# picostepknobs_dispoffset.net
KiCad netlist of a schematic drawn in EAGLE
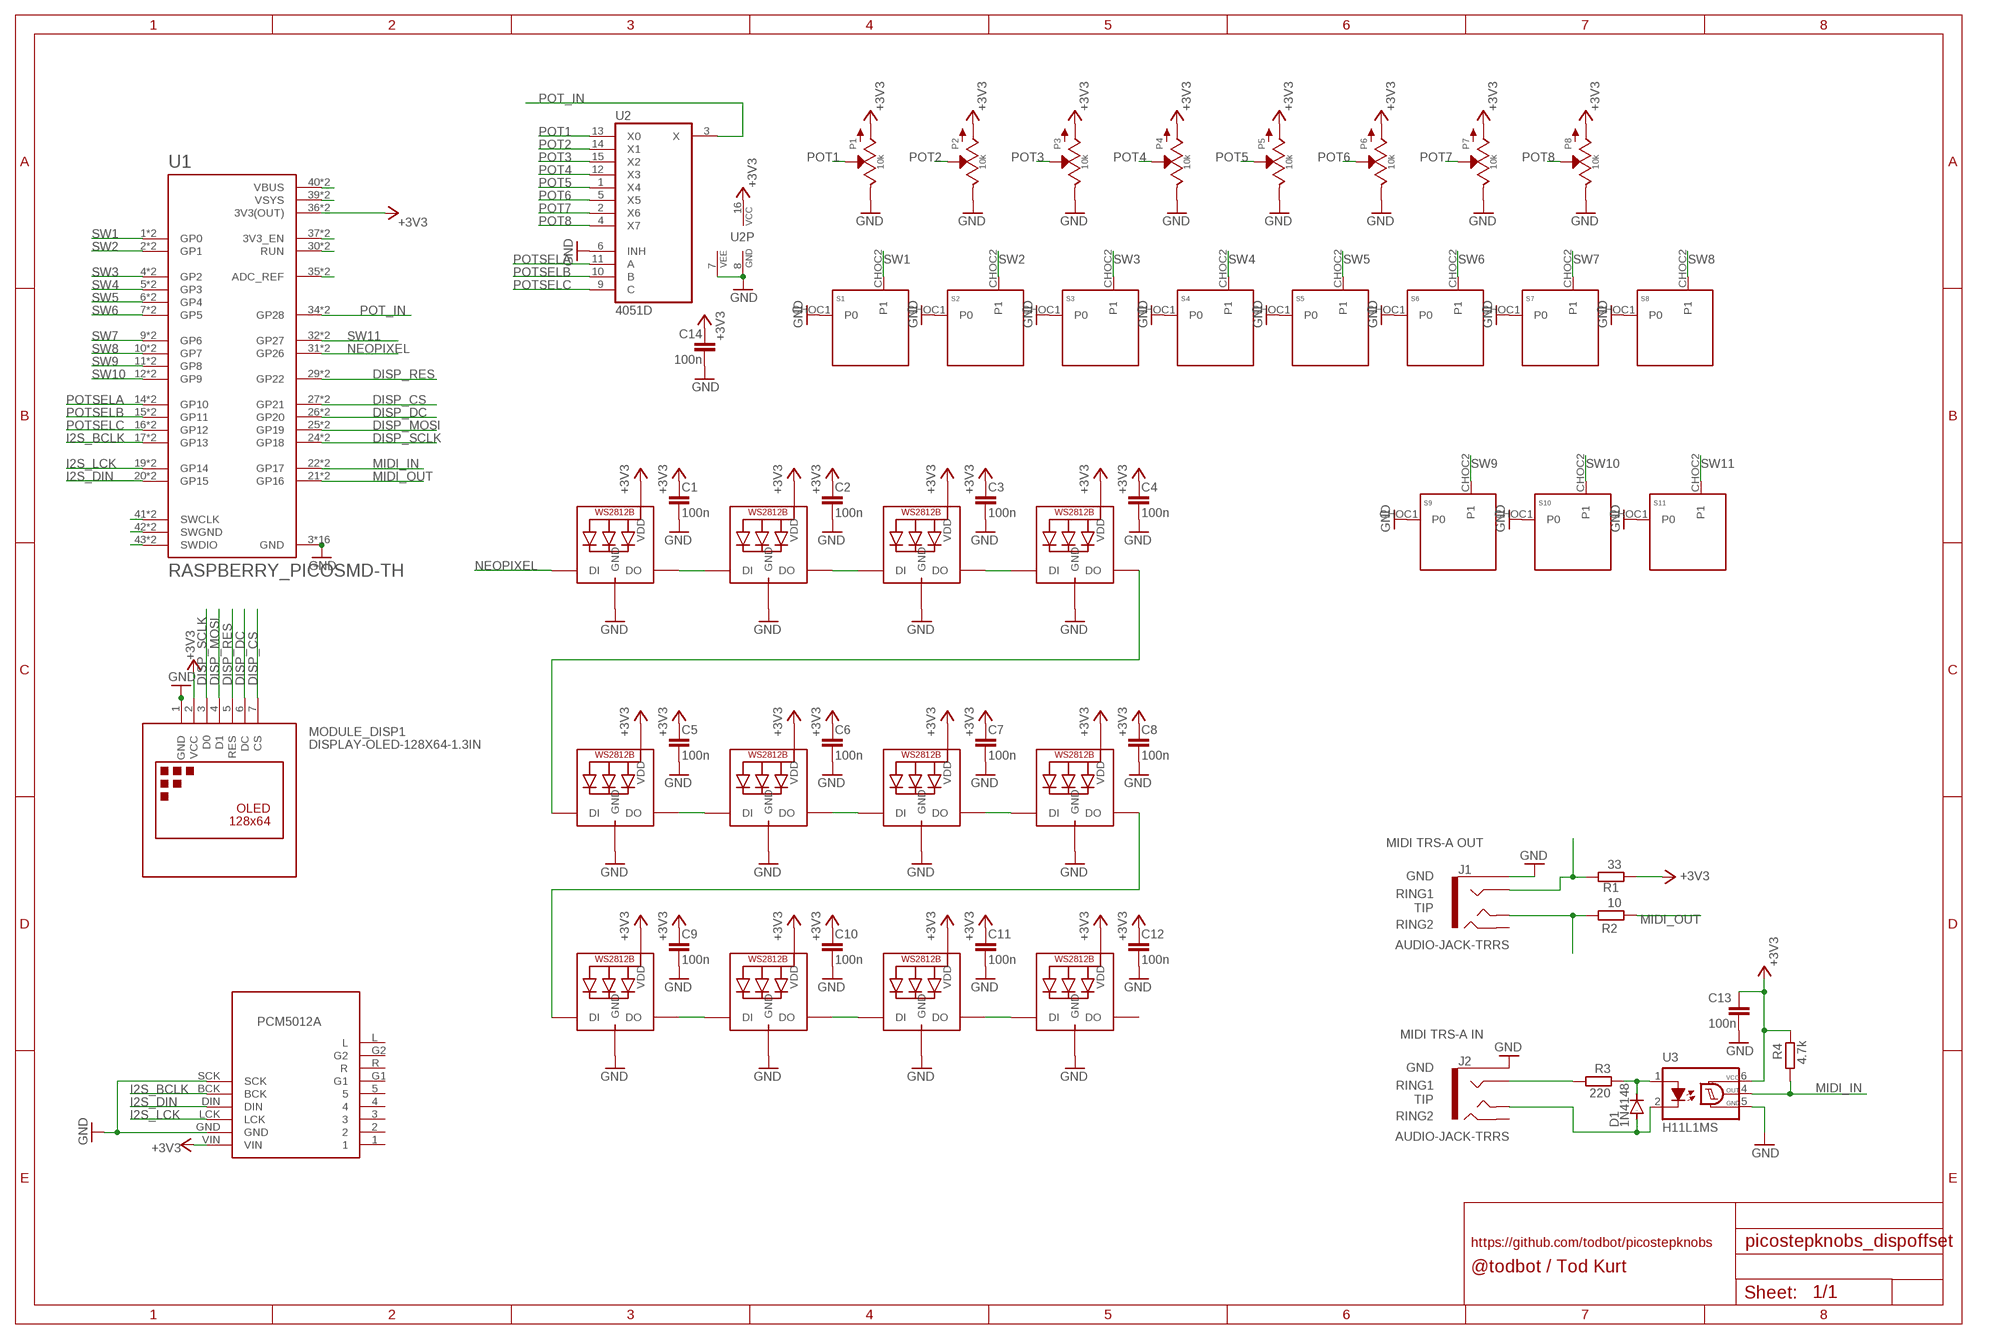
[diagram p0: schematic, sheet 1]

(export (version "E")
  (design (tool "Eeschema 10.0.6"))
  (components
    (comp (ref "C1")
      (value "100n")
      (footprint "eagle-import:C0805")
      (libsource (lib "eagle-import") (part "C-EUC0805"))
    )
    (comp (ref "C2")
      (value "100n")
      (footprint "eagle-import:C0805")
      (libsource (lib "eagle-import") (part "C-EUC0805"))
    )
    (comp (ref "C3")
      (value "100n")
      (footprint "eagle-import:C0805")
      (libsource (lib "eagle-import") (part "C-EUC0805"))
    )
    (comp (ref "C4")
      (value "100n")
      (footprint "eagle-import:C0805")
      (libsource (lib "eagle-import") (part "C-EUC0805"))
    )
    (comp (ref "C5")
      (value "100n")
      (footprint "eagle-import:C0805")
      (libsource (lib "eagle-import") (part "C-EUC0805"))
    )
    (comp (ref "C6")
      (value "100n")
      (footprint "eagle-import:C0805")
      (libsource (lib "eagle-import") (part "C-EUC0805"))
    )
    (comp (ref "C7")
      (value "100n")
      (footprint "eagle-import:C0805")
      (libsource (lib "eagle-import") (part "C-EUC0805"))
    )
    (comp (ref "C8")
      (value "100n")
      (footprint "eagle-import:C0805")
      (libsource (lib "eagle-import") (part "C-EUC0805"))
    )
    (comp (ref "C9")
      (value "100n")
      (footprint "eagle-import:C0805")
      (libsource (lib "eagle-import") (part "C-EUC0805"))
    )
    (comp (ref "C10")
      (value "100n")
      (footprint "eagle-import:C0805")
      (libsource (lib "eagle-import") (part "C-EUC0805"))
    )
    (comp (ref "C11")
      (value "100n")
      (footprint "eagle-import:C0805")
      (libsource (lib "eagle-import") (part "C-EUC0805"))
    )
    (comp (ref "C12")
      (value "100n")
      (footprint "eagle-import:C0805")
      (libsource (lib "eagle-import") (part "C-EUC0805"))
    )
    (comp (ref "C13")
      (value "100n")
      (footprint "eagle-import:C0805")
      (libsource (lib "eagle-import") (part "C-EUC0805"))
    )
    (comp (ref "C14")
      (value "100n")
      (footprint "eagle-import:C0805")
      (libsource (lib "eagle-import") (part "C-EUC0805"))
    )
    (comp (ref "D1")
      (value "1N4148")
      (footprint "eagle-import:SOD123")
      (libsource (lib "eagle-import") (part "DIODE-SOD123"))
    )
    (comp (ref "J1")
      (value "AUDIO-JACK-TRRS")
      (footprint "eagle-import:PJ-320D_SPARKFUN")
      (fields (field (name "MPN") "PJ-320D") (field (name "LCSC") "C431535"))
      (libsource (lib "eagle-import") (part "AUDIO-JACK-TRRS"))
    )
    (comp (ref "J2")
      (value "AUDIO-JACK-TRRS")
      (footprint "eagle-import:PJ-320D_SPARKFUN")
      (fields (field (name "MPN") "PJ-320D"))
      (libsource (lib "eagle-import") (part "AUDIO-JACK-TRRS"))
    )
    (comp (ref "LED1")
      (value "WS2812B3535")
      (footprint "eagle-import:LED3535")
      (libsource (lib "eagle-import") (part "WS2812B3535"))
    )
    (comp (ref "LED2")
      (value "WS2812B3535")
      (footprint "eagle-import:LED3535")
      (libsource (lib "eagle-import") (part "WS2812B3535"))
    )
    (comp (ref "LED3")
      (value "WS2812B3535")
      (footprint "eagle-import:LED3535")
      (libsource (lib "eagle-import") (part "WS2812B3535"))
    )
    (comp (ref "LED4")
      (value "WS2812B3535")
      (footprint "eagle-import:LED3535")
      (libsource (lib "eagle-import") (part "WS2812B3535"))
    )
    (comp (ref "LED5")
      (value "WS2812B3535")
      (footprint "eagle-import:LED3535")
      (libsource (lib "eagle-import") (part "WS2812B3535"))
    )
    (comp (ref "LED6")
      (value "WS2812B3535")
      (footprint "eagle-import:LED3535")
      (libsource (lib "eagle-import") (part "WS2812B3535"))
    )
    (comp (ref "LED7")
      (value "WS2812B3535")
      (footprint "eagle-import:LED3535")
      (libsource (lib "eagle-import") (part "WS2812B3535"))
    )
    (comp (ref "LED8")
      (value "WS2812B3535")
      (footprint "eagle-import:LED3535")
      (libsource (lib "eagle-import") (part "WS2812B3535"))
    )
    (comp (ref "LED9")
      (value "WS2812B3535")
      (footprint "eagle-import:LED3535")
      (libsource (lib "eagle-import") (part "WS2812B3535"))
    )
    (comp (ref "LED10")
      (value "WS2812B3535")
      (footprint "eagle-import:LED3535")
      (libsource (lib "eagle-import") (part "WS2812B3535"))
    )
    (comp (ref "LED11")
      (value "WS2812B3535")
      (footprint "eagle-import:LED3535")
      (libsource (lib "eagle-import") (part "WS2812B3535"))
    )
    (comp (ref "LED12")
      (value "WS2812B3535")
      (footprint "eagle-import:LED3535")
      (libsource (lib "eagle-import") (part "WS2812B3535"))
    )
    (comp (ref "MODULE_DISP1")
      (value "DISPLAY-OLED-128X64-1.3IN")
      (footprint "eagle-import:DISPLAY-OLED-128X64-1.3IN")
      (libsource (lib "eagle-import") (part "DISPLAY-OLED-128X64-1.3IN"))
    )
    (comp (ref "MODULE_PCM5102A")
      (value "I2S_PCM_51XX_SOUNDCARD")
      (footprint "eagle-import:I2S_PCM_5100_SOUNDCARD")
      (libsource (lib "eagle-import") (part "I2S_PCM_51XX_SOUNDCARD"))
    )
    (comp (ref "P1")
      (value "10k")
      (footprint "eagle-import:OG-POTS_ALPS_POT_VERTICAL_WITHBIGKNOB")
      (libsource (lib "eagle-import") (part "POTZEPHPOT_BIGKNOB"))
    )
    (comp (ref "P2")
      (value "10k")
      (footprint "eagle-import:OG-POTS_ALPS_POT_VERTICAL_WITHBIGKNOB")
      (libsource (lib "eagle-import") (part "POTZEPHPOT_BIGKNOB"))
    )
    (comp (ref "P3")
      (value "10k")
      (footprint "eagle-import:OG-POTS_ALPS_POT_VERTICAL_WITHBIGKNOB")
      (libsource (lib "eagle-import") (part "POTZEPHPOT_BIGKNOB"))
    )
    (comp (ref "P4")
      (value "10k")
      (footprint "eagle-import:OG-POTS_ALPS_POT_VERTICAL_WITHBIGKNOB")
      (libsource (lib "eagle-import") (part "POTZEPHPOT_BIGKNOB"))
    )
    (comp (ref "P5")
      (value "10k")
      (footprint "eagle-import:OG-POTS_ALPS_POT_VERTICAL_WITHBIGKNOB")
      (libsource (lib "eagle-import") (part "POTZEPHPOT_BIGKNOB"))
    )
    (comp (ref "P6")
      (value "10k")
      (footprint "eagle-import:OG-POTS_ALPS_POT_VERTICAL_WITHBIGKNOB")
      (libsource (lib "eagle-import") (part "POTZEPHPOT_BIGKNOB"))
    )
    (comp (ref "P7")
      (value "10k")
      (footprint "eagle-import:OG-POTS_ALPS_POT_VERTICAL_WITHBIGKNOB")
      (libsource (lib "eagle-import") (part "POTZEPHPOT_BIGKNOB"))
    )
    (comp (ref "P8")
      (value "10k")
      (footprint "eagle-import:OG-POTS_ALPS_POT_VERTICAL_WITHBIGKNOB")
      (libsource (lib "eagle-import") (part "POTZEPHPOT_BIGKNOB"))
    )
    (comp (ref "R1")
      (value "33")
      (footprint "eagle-import:R0805")
      (libsource (lib "eagle-import") (part "R-EU_R0805"))
    )
    (comp (ref "R2")
      (value "10")
      (footprint "eagle-import:R0805")
      (libsource (lib "eagle-import") (part "R-EU_R0805"))
    )
    (comp (ref "R3")
      (value "220")
      (footprint "eagle-import:R0805")
      (libsource (lib "eagle-import") (part "R-EU_R0805"))
    )
    (comp (ref "R4")
      (value "4.7k")
      (footprint "eagle-import:R0805")
      (libsource (lib "eagle-import") (part "R-EU_R0805"))
    )
    (comp (ref "S1")
      (value "KEYSWITCH-PLAIN-CHOC-1U")
      (footprint "eagle-import:CHOC-1U")
      (libsource (lib "eagle-import") (part "KEYSWITCH-PLAIN-CHOC-1U"))
    )
    (comp (ref "S2")
      (value "KEYSWITCH-PLAIN-CHOC-1U")
      (footprint "eagle-import:CHOC-1U")
      (libsource (lib "eagle-import") (part "KEYSWITCH-PLAIN-CHOC-1U"))
    )
    (comp (ref "S3")
      (value "KEYSWITCH-PLAIN-CHOC-1U")
      (footprint "eagle-import:CHOC-1U")
      (libsource (lib "eagle-import") (part "KEYSWITCH-PLAIN-CHOC-1U"))
    )
    (comp (ref "S4")
      (value "KEYSWITCH-PLAIN-CHOC-1U")
      (footprint "eagle-import:CHOC-1U")
      (libsource (lib "eagle-import") (part "KEYSWITCH-PLAIN-CHOC-1U"))
    )
    (comp (ref "S5")
      (value "KEYSWITCH-PLAIN-CHOC-1U")
      (footprint "eagle-import:CHOC-1U")
      (libsource (lib "eagle-import") (part "KEYSWITCH-PLAIN-CHOC-1U"))
    )
    (comp (ref "S6")
      (value "KEYSWITCH-PLAIN-CHOC-1U")
      (footprint "eagle-import:CHOC-1U")
      (libsource (lib "eagle-import") (part "KEYSWITCH-PLAIN-CHOC-1U"))
    )
    (comp (ref "S7")
      (value "KEYSWITCH-PLAIN-CHOC-1U")
      (footprint "eagle-import:CHOC-1U")
      (libsource (lib "eagle-import") (part "KEYSWITCH-PLAIN-CHOC-1U"))
    )
    (comp (ref "S8")
      (value "KEYSWITCH-PLAIN-CHOC-1U")
      (footprint "eagle-import:CHOC-1U")
      (libsource (lib "eagle-import") (part "KEYSWITCH-PLAIN-CHOC-1U"))
    )
    (comp (ref "S9")
      (value "KEYSWITCH-PLAIN-CHOC-1U")
      (footprint "eagle-import:CHOC-1U")
      (libsource (lib "eagle-import") (part "KEYSWITCH-PLAIN-CHOC-1U"))
    )
    (comp (ref "S10")
      (value "KEYSWITCH-PLAIN-CHOC-1U")
      (footprint "eagle-import:CHOC-1U")
      (libsource (lib "eagle-import") (part "KEYSWITCH-PLAIN-CHOC-1U"))
    )
    (comp (ref "S11")
      (value "KEYSWITCH-PLAIN-CHOC-1U")
      (footprint "eagle-import:CHOC-1U")
      (libsource (lib "eagle-import") (part "KEYSWITCH-PLAIN-CHOC-1U"))
    )
    (comp (ref "U1")
      (value "RASPBERRY_PICOSMD-TH")
      (footprint "eagle-import:PICO-PKG")
      (libsource (lib "eagle-import") (part "RASPBERRY_PICOSMD-TH"))
    )
    (comp (ref "U2")
      (value "4051D")
      (footprint "eagle-import:SO16")
      (libsource (lib "eagle-import") (part "4051D"))
    )
    (comp (ref "U3")
      (value "H11L1MS")
      (footprint "eagle-import:DIL6-SMD")
      (libsource (lib "eagle-import") (part "H11LMS1"))
    )
  )
  (nets
    (net (code "1") (name "+3V3") (class "Default")
      (node (ref "C1") (pin "1") (pinfunction "1_1") (pintype "passive"))
      (node (ref "C10") (pin "1") (pinfunction "1_1") (pintype "passive"))
      (node (ref "C11") (pin "1") (pinfunction "1_1") (pintype "passive"))
      (node (ref "C12") (pin "1") (pinfunction "1_1") (pintype "passive"))
      (node (ref "C13") (pin "1") (pinfunction "1_1") (pintype "passive"))
      (node (ref "C14") (pin "1") (pinfunction "1_1") (pintype "passive"))
      (node (ref "C2") (pin "1") (pinfunction "1_1") (pintype "passive"))
      (node (ref "C3") (pin "1") (pinfunction "1_1") (pintype "passive"))
      (node (ref "C4") (pin "1") (pinfunction "1_1") (pintype "passive"))
      (node (ref "C5") (pin "1") (pinfunction "1_1") (pintype "passive"))
      (node (ref "C6") (pin "1") (pinfunction "1_1") (pintype "passive"))
      (node (ref "C7") (pin "1") (pinfunction "1_1") (pintype "passive"))
      (node (ref "C8") (pin "1") (pinfunction "1_1") (pintype "passive"))
      (node (ref "C9") (pin "1") (pinfunction "1_1") (pintype "passive"))
      (node (ref "LED1") (pin "2") (pinfunction "VDD_2") (pintype "power_in"))
      (node (ref "LED10") (pin "2") (pinfunction "VDD_2") (pintype "power_in"))
      (node (ref "LED11") (pin "2") (pinfunction "VDD_2") (pintype "power_in"))
      (node (ref "LED12") (pin "2") (pinfunction "VDD_2") (pintype "power_in"))
      (node (ref "LED2") (pin "2") (pinfunction "VDD_2") (pintype "power_in"))
      (node (ref "LED3") (pin "2") (pinfunction "VDD_2") (pintype "power_in"))
      (node (ref "LED4") (pin "2") (pinfunction "VDD_2") (pintype "power_in"))
      (node (ref "LED5") (pin "2") (pinfunction "VDD_2") (pintype "power_in"))
      (node (ref "LED6") (pin "2") (pinfunction "VDD_2") (pintype "power_in"))
      (node (ref "LED7") (pin "2") (pinfunction "VDD_2") (pintype "power_in"))
      (node (ref "LED8") (pin "2") (pinfunction "VDD_2") (pintype "power_in"))
      (node (ref "LED9") (pin "2") (pinfunction "VDD_2") (pintype "power_in"))
      (node (ref "MODULE_DISP1") (pin "2") (pinfunction "VCC_2") (pintype "power_in"))
      (node (ref "MODULE_PCM5102A") (pin "VIN") (pinfunction "VIN_VIN") (pintype "bidirectional"))
      (node (ref "P1") (pin "P$3") (pinfunction "A_P$3") (pintype "passive"))
      (node (ref "P2") (pin "P$3") (pinfunction "A_P$3") (pintype "passive"))
      (node (ref "P3") (pin "P$3") (pinfunction "A_P$3") (pintype "passive"))
      (node (ref "P4") (pin "P$3") (pinfunction "A_P$3") (pintype "passive"))
      (node (ref "P5") (pin "P$3") (pinfunction "A_P$3") (pintype "passive"))
      (node (ref "P6") (pin "P$3") (pinfunction "A_P$3") (pintype "passive"))
      (node (ref "P7") (pin "P$3") (pinfunction "A_P$3") (pintype "passive"))
      (node (ref "P8") (pin "P$3") (pinfunction "A_P$3") (pintype "passive"))
      (node (ref "R1") (pin "2") (pinfunction "2_2") (pintype "passive"))
      (node (ref "R4") (pin "1") (pinfunction "1_1") (pintype "passive"))
      (node (ref "U1") (pin "36") (pinfunction "3V3(OUT)_36") (pintype "power_in"))
      (node (ref "U1") (pin "P$36") (pinfunction "3V3(OUT)_P$36") (pintype "power_in"))
      (node (ref "U2") (pin "16") (pinfunction "VCC_16") (pintype "power_in"))
      (node (ref "U3") (pin "6") (pinfunction "VCC_6") (pintype "power_in"))
    )
    (net (code "2") (name "/DISP_CS") (class "Default")
      (node (ref "MODULE_DISP1") (pin "7") (pinfunction "CS_7") (pintype "bidirectional"))
      (node (ref "U1") (pin "27") (pinfunction "GP21_27") (pintype "bidirectional"))
      (node (ref "U1") (pin "P$27") (pinfunction "GP21_P$27") (pintype "bidirectional"))
    )
    (net (code "3") (name "/DISP_DC") (class "Default")
      (node (ref "MODULE_DISP1") (pin "6") (pinfunction "DC_6") (pintype "bidirectional"))
      (node (ref "U1") (pin "26") (pinfunction "GP20_26") (pintype "bidirectional"))
      (node (ref "U1") (pin "P$26") (pinfunction "GP20_P$26") (pintype "bidirectional"))
    )
    (net (code "4") (name "/DISP_MOSI") (class "Default")
      (node (ref "MODULE_DISP1") (pin "4") (pinfunction "D1_4") (pintype "bidirectional"))
      (node (ref "U1") (pin "25") (pinfunction "GP19_25") (pintype "bidirectional"))
      (node (ref "U1") (pin "P$25") (pinfunction "GP19_P$25") (pintype "bidirectional"))
    )
    (net (code "5") (name "/DISP_RES") (class "Default")
      (node (ref "MODULE_DISP1") (pin "5") (pinfunction "RES_5") (pintype "bidirectional"))
      (node (ref "U1") (pin "29") (pinfunction "GP22_29") (pintype "bidirectional"))
      (node (ref "U1") (pin "P$29") (pinfunction "GP22_P$29") (pintype "bidirectional"))
    )
    (net (code "6") (name "/DISP_SCLK") (class "Default")
      (node (ref "MODULE_DISP1") (pin "3") (pinfunction "D0_3") (pintype "bidirectional"))
      (node (ref "U1") (pin "24") (pinfunction "GP18_24") (pintype "bidirectional"))
      (node (ref "U1") (pin "P$24") (pinfunction "GP18_P$24") (pintype "bidirectional"))
    )
    (net (code "7") (name "/I2S_BCLK") (class "Default")
      (node (ref "MODULE_PCM5102A") (pin "BCK") (pinfunction "BCK_BCK") (pintype "bidirectional"))
      (node (ref "U1") (pin "17") (pinfunction "GP13_17") (pintype "bidirectional"))
      (node (ref "U1") (pin "P$17") (pinfunction "GP13_P$17") (pintype "bidirectional"))
    )
    (net (code "8") (name "/I2S_DIN") (class "Default")
      (node (ref "MODULE_PCM5102A") (pin "DIN") (pinfunction "DIN_DIN") (pintype "bidirectional"))
      (node (ref "U1") (pin "20") (pinfunction "GP15_20") (pintype "bidirectional"))
      (node (ref "U1") (pin "P$20") (pinfunction "GP15_P$20") (pintype "bidirectional"))
    )
    (net (code "9") (name "/I2S_LCK") (class "Default")
      (node (ref "MODULE_PCM5102A") (pin "LCK") (pinfunction "LCK_LCK") (pintype "bidirectional"))
      (node (ref "U1") (pin "19") (pinfunction "GP14_19") (pintype "bidirectional"))
      (node (ref "U1") (pin "P$19") (pinfunction "GP14_P$19") (pintype "bidirectional"))
    )
    (net (code "10") (name "/MIDI_IN") (class "Default")
      (node (ref "R4") (pin "2") (pinfunction "2_2") (pintype "passive"))
      (node (ref "U1") (pin "22") (pinfunction "GP17_22") (pintype "bidirectional"))
      (node (ref "U1") (pin "P$22") (pinfunction "GP17_P$22") (pintype "bidirectional"))
      (node (ref "U3") (pin "4") (pinfunction "OUT_4") (pintype "output"))
    )
    (net (code "11") (name "/MIDI_OUT") (class "Default")
      (node (ref "R2") (pin "2") (pinfunction "2_2") (pintype "passive"))
      (node (ref "U1") (pin "21") (pinfunction "GP16_21") (pintype "bidirectional"))
      (node (ref "U1") (pin "P$21") (pinfunction "GP16_P$21") (pintype "bidirectional"))
    )
    (net (code "12") (name "/NEOPIXEL") (class "Default")
      (node (ref "LED1") (pin "1") (pinfunction "DI_1") (pintype "input"))
      (node (ref "U1") (pin "31") (pinfunction "GP26_31") (pintype "bidirectional"))
      (node (ref "U1") (pin "P$31") (pinfunction "GP26_P$31") (pintype "bidirectional"))
    )
    (net (code "13") (name "/POT1") (class "Default")
      (node (ref "P1") (pin "P$2") (pinfunction "S_P$2") (pintype "passive"))
      (node (ref "U2") (pin "13") (pinfunction "X0_13") (pintype "bidirectional"))
    )
    (net (code "14") (name "/POT2") (class "Default")
      (node (ref "P2") (pin "P$2") (pinfunction "S_P$2") (pintype "passive"))
      (node (ref "U2") (pin "14") (pinfunction "X1_14") (pintype "bidirectional"))
    )
    (net (code "15") (name "/POT3") (class "Default")
      (node (ref "P3") (pin "P$2") (pinfunction "S_P$2") (pintype "passive"))
      (node (ref "U2") (pin "15") (pinfunction "X2_15") (pintype "bidirectional"))
    )
    (net (code "16") (name "/POT4") (class "Default")
      (node (ref "P4") (pin "P$2") (pinfunction "S_P$2") (pintype "passive"))
      (node (ref "U2") (pin "12") (pinfunction "X3_12") (pintype "bidirectional"))
    )
    (net (code "17") (name "/POT5") (class "Default")
      (node (ref "P5") (pin "P$2") (pinfunction "S_P$2") (pintype "passive"))
      (node (ref "U2") (pin "1") (pinfunction "X4_1") (pintype "bidirectional"))
    )
    (net (code "18") (name "/POT6") (class "Default")
      (node (ref "P6") (pin "P$2") (pinfunction "S_P$2") (pintype "passive"))
      (node (ref "U2") (pin "5") (pinfunction "X5_5") (pintype "bidirectional"))
    )
    (net (code "19") (name "/POT7") (class "Default")
      (node (ref "P7") (pin "P$2") (pinfunction "S_P$2") (pintype "passive"))
      (node (ref "U2") (pin "2") (pinfunction "X6_2") (pintype "bidirectional"))
    )
    (net (code "20") (name "/POT8") (class "Default")
      (node (ref "P8") (pin "P$2") (pinfunction "S_P$2") (pintype "passive"))
      (node (ref "U2") (pin "4") (pinfunction "X7_4") (pintype "bidirectional"))
    )
    (net (code "21") (name "/POTSELA") (class "Default")
      (node (ref "U1") (pin "14") (pinfunction "GP10_14") (pintype "bidirectional"))
      (node (ref "U1") (pin "P$14") (pinfunction "GP10_P$14") (pintype "bidirectional"))
      (node (ref "U2") (pin "11") (pinfunction "A_11") (pintype "input"))
    )
    (net (code "22") (name "/POTSELB") (class "Default")
      (node (ref "U1") (pin "15") (pinfunction "GP11_15") (pintype "bidirectional"))
      (node (ref "U1") (pin "P$15") (pinfunction "GP11_P$15") (pintype "bidirectional"))
      (node (ref "U2") (pin "10") (pinfunction "B_10") (pintype "input"))
    )
    (net (code "23") (name "/POTSELC") (class "Default")
      (node (ref "U1") (pin "16") (pinfunction "GP12_16") (pintype "bidirectional"))
      (node (ref "U1") (pin "P$16") (pinfunction "GP12_P$16") (pintype "bidirectional"))
      (node (ref "U2") (pin "9") (pinfunction "C_9") (pintype "input"))
    )
    (net (code "24") (name "/POT_IN") (class "Default")
      (node (ref "U1") (pin "34") (pinfunction "GP28_34") (pintype "bidirectional"))
      (node (ref "U1") (pin "P$34") (pinfunction "GP28_P$34") (pintype "bidirectional"))
      (node (ref "U2") (pin "3") (pinfunction "X_3") (pintype "bidirectional"))
    )
    (net (code "25") (name "/SW1") (class "Default")
      (node (ref "S1") (pin "CHOC2") (pinfunction "P1_CHOC2") (pintype "bidirectional"))
      (node (ref "U1") (pin "1") (pinfunction "GP0_1") (pintype "bidirectional"))
      (node (ref "U1") (pin "P$1") (pinfunction "GP0_P$1") (pintype "bidirectional"))
    )
    (net (code "26") (name "/SW2") (class "Default")
      (node (ref "S2") (pin "CHOC2") (pinfunction "P1_CHOC2") (pintype "bidirectional"))
      (node (ref "U1") (pin "2") (pinfunction "GP1_2") (pintype "bidirectional"))
      (node (ref "U1") (pin "P$2") (pinfunction "GP1_P$2") (pintype "bidirectional"))
    )
    (net (code "27") (name "/SW3") (class "Default")
      (node (ref "S3") (pin "CHOC2") (pinfunction "P1_CHOC2") (pintype "bidirectional"))
      (node (ref "U1") (pin "4") (pinfunction "GP2_4") (pintype "bidirectional"))
      (node (ref "U1") (pin "P$4") (pinfunction "GP2_P$4") (pintype "bidirectional"))
    )
    (net (code "28") (name "/SW4") (class "Default")
      (node (ref "S4") (pin "CHOC2") (pinfunction "P1_CHOC2") (pintype "bidirectional"))
      (node (ref "U1") (pin "5") (pinfunction "GP3_5") (pintype "bidirectional"))
      (node (ref "U1") (pin "P$5") (pinfunction "GP3_P$5") (pintype "bidirectional"))
    )
    (net (code "29") (name "/SW5") (class "Default")
      (node (ref "S5") (pin "CHOC2") (pinfunction "P1_CHOC2") (pintype "bidirectional"))
      (node (ref "U1") (pin "6") (pinfunction "GP4_6") (pintype "bidirectional"))
      (node (ref "U1") (pin "P$6") (pinfunction "GP4_P$6") (pintype "bidirectional"))
    )
    (net (code "30") (name "/SW6") (class "Default")
      (node (ref "S6") (pin "CHOC2") (pinfunction "P1_CHOC2") (pintype "bidirectional"))
      (node (ref "U1") (pin "7") (pinfunction "GP5_7") (pintype "bidirectional"))
      (node (ref "U1") (pin "P$7") (pinfunction "GP5_P$7") (pintype "bidirectional"))
    )
    (net (code "31") (name "/SW7") (class "Default")
      (node (ref "S7") (pin "CHOC2") (pinfunction "P1_CHOC2") (pintype "bidirectional"))
      (node (ref "U1") (pin "9") (pinfunction "GP6_9") (pintype "bidirectional"))
      (node (ref "U1") (pin "P$9") (pinfunction "GP6_P$9") (pintype "bidirectional"))
    )
    (net (code "32") (name "/SW8") (class "Default")
      (node (ref "S8") (pin "CHOC2") (pinfunction "P1_CHOC2") (pintype "bidirectional"))
      (node (ref "U1") (pin "10") (pinfunction "GP7_10") (pintype "bidirectional"))
      (node (ref "U1") (pin "P$10") (pinfunction "GP7_P$10") (pintype "bidirectional"))
    )
    (net (code "33") (name "/SW9") (class "Default")
      (node (ref "S9") (pin "CHOC2") (pinfunction "P1_CHOC2") (pintype "bidirectional"))
      (node (ref "U1") (pin "11") (pinfunction "GP8_11") (pintype "bidirectional"))
      (node (ref "U1") (pin "P$11") (pinfunction "GP8_P$11") (pintype "bidirectional"))
    )
    (net (code "34") (name "/SW10") (class "Default")
      (node (ref "S10") (pin "CHOC2") (pinfunction "P1_CHOC2") (pintype "bidirectional"))
      (node (ref "U1") (pin "12") (pinfunction "GP9_12") (pintype "bidirectional"))
      (node (ref "U1") (pin "P$12") (pinfunction "GP9_P$12") (pintype "bidirectional"))
    )
    (net (code "35") (name "/SW11") (class "Default")
      (node (ref "S11") (pin "CHOC2") (pinfunction "P1_CHOC2") (pintype "bidirectional"))
      (node (ref "U1") (pin "32") (pinfunction "GP27_32") (pintype "bidirectional"))
      (node (ref "U1") (pin "P$32") (pinfunction "GP27_P$32") (pintype "bidirectional"))
    )
    (net (code "36") (name "GND") (class "Default")
      (node (ref "C1") (pin "2") (pinfunction "2_2") (pintype "passive"))
      (node (ref "C10") (pin "2") (pinfunction "2_2") (pintype "passive"))
      (node (ref "C11") (pin "2") (pinfunction "2_2") (pintype "passive"))
      (node (ref "C12") (pin "2") (pinfunction "2_2") (pintype "passive"))
      (node (ref "C13") (pin "2") (pinfunction "2_2") (pintype "passive"))
      (node (ref "C14") (pin "2") (pinfunction "2_2") (pintype "passive"))
      (node (ref "C2") (pin "2") (pinfunction "2_2") (pintype "passive"))
      (node (ref "C3") (pin "2") (pinfunction "2_2") (pintype "passive"))
      (node (ref "C4") (pin "2") (pinfunction "2_2") (pintype "passive"))
      (node (ref "C5") (pin "2") (pinfunction "2_2") (pintype "passive"))
      (node (ref "C6") (pin "2") (pinfunction "2_2") (pintype "passive"))
      (node (ref "C7") (pin "2") (pinfunction "2_2") (pintype "passive"))
      (node (ref "C8") (pin "2") (pinfunction "2_2") (pintype "passive"))
      (node (ref "C9") (pin "2") (pinfunction "2_2") (pintype "passive"))
      (node (ref "J1") (pin "EARTH") (pinfunction "EARTH_EARTH") (pintype "bidirectional"))
      (node (ref "J2") (pin "EARTH") (pinfunction "EARTH_EARTH") (pintype "bidirectional"))
      (node (ref "LED1") (pin "4") (pinfunction "GND_4") (pintype "power_in"))
      (node (ref "LED10") (pin "4") (pinfunction "GND_4") (pintype "power_in"))
      (node (ref "LED11") (pin "4") (pinfunction "GND_4") (pintype "power_in"))
      (node (ref "LED12") (pin "4") (pinfunction "GND_4") (pintype "power_in"))
      (node (ref "LED2") (pin "4") (pinfunction "GND_4") (pintype "power_in"))
      (node (ref "LED3") (pin "4") (pinfunction "GND_4") (pintype "power_in"))
      (node (ref "LED4") (pin "4") (pinfunction "GND_4") (pintype "power_in"))
      (node (ref "LED5") (pin "4") (pinfunction "GND_4") (pintype "power_in"))
      (node (ref "LED6") (pin "4") (pinfunction "GND_4") (pintype "power_in"))
      (node (ref "LED7") (pin "4") (pinfunction "GND_4") (pintype "power_in"))
      (node (ref "LED8") (pin "4") (pinfunction "GND_4") (pintype "power_in"))
      (node (ref "LED9") (pin "4") (pinfunction "GND_4") (pintype "power_in"))
      (node (ref "MODULE_DISP1") (pin "1") (pinfunction "GND_1") (pintype "power_in"))
      (node (ref "MODULE_PCM5102A") (pin "GND") (pinfunction "GND_GND") (pintype "bidirectional"))
      (node (ref "MODULE_PCM5102A") (pin "SCK") (pinfunction "SCK_SCK") (pintype "bidirectional"))
      (node (ref "P1") (pin "P$1") (pinfunction "E_P$1") (pintype "passive"))
      (node (ref "P2") (pin "P$1") (pinfunction "E_P$1") (pintype "passive"))
      (node (ref "P3") (pin "P$1") (pinfunction "E_P$1") (pintype "passive"))
      (node (ref "P4") (pin "P$1") (pinfunction "E_P$1") (pintype "passive"))
      (node (ref "P5") (pin "P$1") (pinfunction "E_P$1") (pintype "passive"))
      (node (ref "P6") (pin "P$1") (pinfunction "E_P$1") (pintype "passive"))
      (node (ref "P7") (pin "P$1") (pinfunction "E_P$1") (pintype "passive"))
      (node (ref "P8") (pin "P$1") (pinfunction "E_P$1") (pintype "passive"))
      (node (ref "S1") (pin "CHOC1") (pinfunction "P0_CHOC1") (pintype "bidirectional"))
      (node (ref "S10") (pin "CHOC1") (pinfunction "P0_CHOC1") (pintype "bidirectional"))
      (node (ref "S11") (pin "CHOC1") (pinfunction "P0_CHOC1") (pintype "bidirectional"))
      (node (ref "S2") (pin "CHOC1") (pinfunction "P0_CHOC1") (pintype "bidirectional"))
      (node (ref "S3") (pin "CHOC1") (pinfunction "P0_CHOC1") (pintype "bidirectional"))
      (node (ref "S4") (pin "CHOC1") (pinfunction "P0_CHOC1") (pintype "bidirectional"))
      (node (ref "S5") (pin "CHOC1") (pinfunction "P0_CHOC1") (pintype "bidirectional"))
      (node (ref "S6") (pin "CHOC1") (pinfunction "P0_CHOC1") (pintype "bidirectional"))
      (node (ref "S7") (pin "CHOC1") (pinfunction "P0_CHOC1") (pintype "bidirectional"))
      (node (ref "S8") (pin "CHOC1") (pinfunction "P0_CHOC1") (pintype "bidirectional"))
      (node (ref "S9") (pin "CHOC1") (pinfunction "P0_CHOC1") (pintype "bidirectional"))
      (node (ref "U1") (pin "13") (pinfunction "GND_13") (pintype "power_in"))
      (node (ref "U1") (pin "18") (pinfunction "GND_18") (pintype "power_in"))
      (node (ref "U1") (pin "23") (pinfunction "GND_23") (pintype "power_in"))
      (node (ref "U1") (pin "28") (pinfunction "GND_28") (pintype "power_in"))
      (node (ref "U1") (pin "3") (pinfunction "GND_3") (pintype "power_in"))
      (node (ref "U1") (pin "33") (pinfunction "GND_33") (pintype "power_in"))
      (node (ref "U1") (pin "38") (pinfunction "GND_38") (pintype "power_in"))
      (node (ref "U1") (pin "8") (pinfunction "GND_8") (pintype "power_in"))
      (node (ref "U1") (pin "P$13") (pinfunction "GND_P$13") (pintype "power_in"))
      (node (ref "U1") (pin "P$18") (pinfunction "GND_P$18") (pintype "power_in"))
      (node (ref "U1") (pin "P$23") (pinfunction "GND_P$23") (pintype "power_in"))
      (node (ref "U1") (pin "P$28") (pinfunction "GND_P$28") (pintype "power_in"))
      (node (ref "U1") (pin "P$3") (pinfunction "GND_P$3") (pintype "power_in"))
      (node (ref "U1") (pin "P$33") (pinfunction "GND_P$33") (pintype "power_in"))
      (node (ref "U1") (pin "P$38") (pinfunction "GND_P$38") (pintype "power_in"))
      (node (ref "U1") (pin "P$8") (pinfunction "GND_P$8") (pintype "power_in"))
      (node (ref "U2") (pin "6") (pinfunction "INH_6") (pintype "input"))
      (node (ref "U2") (pin "7") (pinfunction "VEE_7") (pintype "power_in"))
      (node (ref "U2") (pin "8") (pinfunction "GND_8") (pintype "power_in"))
      (node (ref "U3") (pin "5") (pinfunction "GND_5") (pintype "power_in"))
    )
    (net (code "37") (name "Net-(J1-PadRING1)") (class "Default")
      (node (ref "J1") (pin "RING1") (pinfunction "RING1_RING1") (pintype "bidirectional"))
      (node (ref "R1") (pin "1") (pinfunction "1_1") (pintype "passive"))
    )
    (net (code "38") (name "Net-(J1-PadTIP)") (class "Default")
      (node (ref "J1") (pin "TIP") (pinfunction "TIP_TIP") (pintype "bidirectional"))
      (node (ref "R2") (pin "1") (pinfunction "1_1") (pintype "passive"))
    )
    (net (code "39") (name "Net-(J2-PadRING1)") (class "Default")
      (node (ref "J2") (pin "RING1") (pinfunction "RING1_RING1") (pintype "bidirectional"))
      (node (ref "R3") (pin "2") (pinfunction "2_2") (pintype "passive"))
    )
    (net (code "40") (name "Net-(LED1-DO)") (class "Default")
      (node (ref "LED1") (pin "3") (pinfunction "DO_3") (pintype "output"))
      (node (ref "LED2") (pin "1") (pinfunction "DI_1") (pintype "input"))
    )
    (net (code "41") (name "Net-(LED2-DO)") (class "Default")
      (node (ref "LED2") (pin "3") (pinfunction "DO_3") (pintype "output"))
      (node (ref "LED3") (pin "1") (pinfunction "DI_1") (pintype "input"))
    )
    (net (code "42") (name "Net-(LED3-DO)") (class "Default")
      (node (ref "LED3") (pin "3") (pinfunction "DO_3") (pintype "output"))
      (node (ref "LED4") (pin "1") (pinfunction "DI_1") (pintype "input"))
    )
    (net (code "43") (name "Net-(LED4-DO)") (class "Default")
      (node (ref "LED4") (pin "3") (pinfunction "DO_3") (pintype "output"))
      (node (ref "LED5") (pin "1") (pinfunction "DI_1") (pintype "input"))
    )
    (net (code "44") (name "Net-(LED5-DO)") (class "Default")
      (node (ref "LED5") (pin "3") (pinfunction "DO_3") (pintype "output"))
      (node (ref "LED6") (pin "1") (pinfunction "DI_1") (pintype "input"))
    )
    (net (code "45") (name "Net-(LED6-DO)") (class "Default")
      (node (ref "LED6") (pin "3") (pinfunction "DO_3") (pintype "output"))
      (node (ref "LED7") (pin "1") (pinfunction "DI_1") (pintype "input"))
    )
    (net (code "46") (name "Net-(LED7-DO)") (class "Default")
      (node (ref "LED7") (pin "3") (pinfunction "DO_3") (pintype "output"))
      (node (ref "LED8") (pin "1") (pinfunction "DI_1") (pintype "input"))
    )
    (net (code "47") (name "Net-(LED8-DO)") (class "Default")
      (node (ref "LED8") (pin "3") (pinfunction "DO_3") (pintype "output"))
      (node (ref "LED9") (pin "1") (pinfunction "DI_1") (pintype "input"))
    )
    (net (code "48") (name "Net-(LED10-DI)") (class "Default")
      (node (ref "LED10") (pin "1") (pinfunction "DI_1") (pintype "input"))
      (node (ref "LED9") (pin "3") (pinfunction "DO_3") (pintype "output"))
    )
    (net (code "49") (name "Net-(LED10-DO)") (class "Default")
      (node (ref "LED10") (pin "3") (pinfunction "DO_3") (pintype "output"))
      (node (ref "LED11") (pin "1") (pinfunction "DI_1") (pintype "input"))
    )
    (net (code "50") (name "Net-(LED11-DO)") (class "Default")
      (node (ref "LED11") (pin "3") (pinfunction "DO_3") (pintype "output"))
      (node (ref "LED12") (pin "1") (pinfunction "DI_1") (pintype "input"))
    )
    (net (code "51") (name "Net-(U1-3V3_EN-Pad37)") (class "Default")
      (node (ref "U1") (pin "37") (pinfunction "3V3_EN_37") (pintype "input"))
      (node (ref "U1") (pin "P$37") (pinfunction "3V3_EN_P$37") (pintype "input"))
    )
    (net (code "52") (name "Net-(U1-ADC_REF-Pad35)") (class "Default")
      (node (ref "U1") (pin "35") (pinfunction "ADC_REF_35") (pintype "input"))
      (node (ref "U1") (pin "P$35") (pinfunction "ADC_REF_P$35") (pintype "input"))
    )
    (net (code "53") (name "Net-(U1-RUN-Pad30)") (class "Default")
      (node (ref "U1") (pin "30") (pinfunction "RUN_30") (pintype "input"))
      (node (ref "U1") (pin "P$30") (pinfunction "RUN_P$30") (pintype "input"))
    )
    (net (code "54") (name "Net-(U1-SWCLK-Pad41)") (class "Default")
      (node (ref "U1") (pin "41") (pinfunction "SWCLK_41") (pintype "input"))
      (node (ref "U1") (pin "P$41") (pinfunction "SWCLK_P$41") (pintype "input"))
    )
    (net (code "55") (name "Net-(U1-SWDIO-Pad43)") (class "Default")
      (node (ref "U1") (pin "43") (pinfunction "SWDIO_43") (pintype "bidirectional"))
      (node (ref "U1") (pin "P$43") (pinfunction "SWDIO_P$43") (pintype "bidirectional"))
    )
    (net (code "56") (name "Net-(U1-SWGND-Pad42)") (class "Default")
      (node (ref "U1") (pin "42") (pinfunction "SWGND_42") (pintype "power_in"))
      (node (ref "U1") (pin "P$42") (pinfunction "SWGND_P$42") (pintype "power_in"))
    )
    (net (code "57") (name "Net-(U1-VBUS-Pad40)") (class "Default")
      (node (ref "U1") (pin "40") (pinfunction "VBUS_40") (pintype "power_in"))
      (node (ref "U1") (pin "P$40") (pinfunction "VBUS_P$40") (pintype "power_in"))
    )
    (net (code "58") (name "Net-(U1-VSYS-Pad39)") (class "Default")
      (node (ref "U1") (pin "39") (pinfunction "VSYS_39") (pintype "power_in"))
      (node (ref "U1") (pin "P$39") (pinfunction "VSYS_P$39") (pintype "power_in"))
    )
    (net (code "59") (name "Net-(U3-A)") (class "Default")
      (node (ref "D1") (pin "C") (pinfunction "C_C") (pintype "passive"))
      (node (ref "R3") (pin "1") (pinfunction "1_1") (pintype "passive"))
      (node (ref "U3") (pin "1") (pinfunction "A_1") (pintype "passive"))
    )
    (net (code "60") (name "Net-(U3-C)") (class "Default")
      (node (ref "D1") (pin "A") (pinfunction "A_A") (pintype "passive"))
      (node (ref "J2") (pin "TIP") (pinfunction "TIP_TIP") (pintype "bidirectional"))
      (node (ref "U3") (pin "2") (pinfunction "C_2") (pintype "passive"))
    )
    (net (code "61") (name "unconnected-(J1-PadRING2)") (class "Default")
      (node (ref "J1") (pin "RING2") (pinfunction "RING2_RING2") (pintype "bidirectional"))
    )
    (net (code "62") (name "unconnected-(J2-PadRING2)") (class "Default")
      (node (ref "J2") (pin "RING2") (pinfunction "RING2_RING2") (pintype "bidirectional"))
    )
    (net (code "63") (name "unconnected-(LED12-DO-Pad3)") (class "Default")
      (node (ref "LED12") (pin "3") (pinfunction "DO_3") (pintype "output"))
    )
    (net (code "64") (name "unconnected-(MODULE_PCM5102A-Pad1)") (class "Default")
      (node (ref "MODULE_PCM5102A") (pin "1") (pinfunction "1_1") (pintype "bidirectional"))
    )
    (net (code "65") (name "unconnected-(MODULE_PCM5102A-Pad2)") (class "Default")
      (node (ref "MODULE_PCM5102A") (pin "2") (pinfunction "2_2") (pintype "bidirectional"))
    )
    (net (code "66") (name "unconnected-(MODULE_PCM5102A-Pad3)") (class "Default")
      (node (ref "MODULE_PCM5102A") (pin "3") (pinfunction "3_3") (pintype "bidirectional"))
    )
    (net (code "67") (name "unconnected-(MODULE_PCM5102A-Pad4)") (class "Default")
      (node (ref "MODULE_PCM5102A") (pin "4") (pinfunction "4_4") (pintype "bidirectional"))
    )
    (net (code "68") (name "unconnected-(MODULE_PCM5102A-Pad5)") (class "Default")
      (node (ref "MODULE_PCM5102A") (pin "5") (pinfunction "5_5") (pintype "bidirectional"))
    )
    (net (code "69") (name "unconnected-(MODULE_PCM5102A-PadG1)") (class "Default")
      (node (ref "MODULE_PCM5102A") (pin "G1") (pinfunction "G1_G1") (pintype "bidirectional"))
    )
    (net (code "70") (name "unconnected-(MODULE_PCM5102A-PadG2)") (class "Default")
      (node (ref "MODULE_PCM5102A") (pin "G2") (pinfunction "G2_G2") (pintype "bidirectional"))
    )
    (net (code "71") (name "unconnected-(MODULE_PCM5102A-PadL)") (class "Default")
      (node (ref "MODULE_PCM5102A") (pin "L") (pinfunction "L_L") (pintype "bidirectional"))
    )
    (net (code "72") (name "unconnected-(MODULE_PCM5102A-PadR)") (class "Default")
      (node (ref "MODULE_PCM5102A") (pin "R") (pinfunction "R_R") (pintype "bidirectional"))
    )
  )
)
